# CANTRICK_MCU.net
KiCad netlist of a schematic drawn in Altium Designer
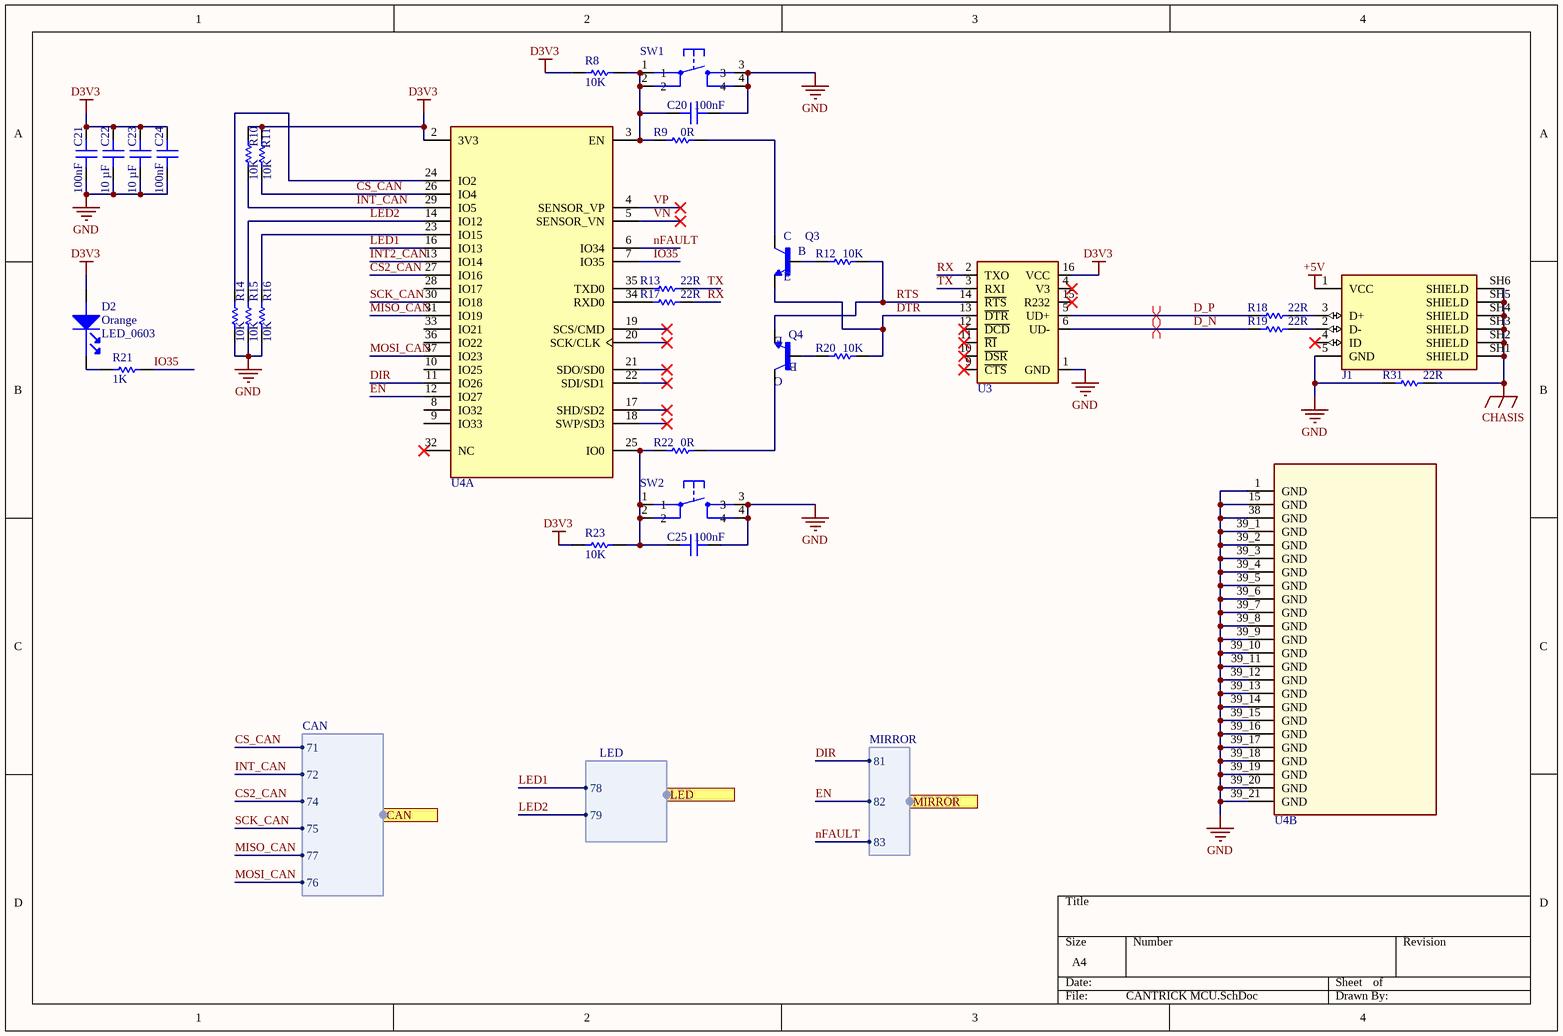
[diagram p0: CANTRICK MCU.SchDoc]

(export (version "E")
  (design (tool "Eeschema 10.0.6"))
  (components
    (comp (ref "C20")
      (value "100nF")
      (footprint "CAP 0603")
      (description "CAP0603 X7R 10UF 10% 10V")
      (fields
        (field (name "PART NUMBER") "GMC10X7R106K10NT")
        (field (name "MANUFACTURER") "Cal-Chip Electronics, Inc.")
      )
      (libsource (lib "Celestial Altium Library - altium_library") (part "Capacitor"))
    )
    (comp (ref "C21")
      (value "100nF")
      (footprint "CAP 0603")
      (description "CAP0603 X7R 10UF 10% 10V")
      (fields
        (field (name "PART NUMBER") "GMC10X7R106K10NT")
        (field (name "MANUFACTURER") "Cal-Chip Electronics, Inc.")
      )
      (libsource (lib "Celestial Altium Library - altium_library") (part "Capacitor"))
    )
    (comp (ref "C22")
      (value "10 µF")
      (footprint "CAP 0603")
      (description "CAP0603 X7R 10UF 10% 10V")
      (fields
        (field (name "PART NUMBER") "GMC10X7R106K10NT")
        (field (name "MANUFACTURER") "Cal-Chip Electronics, Inc.")
      )
      (libsource (lib "Celestial Altium Library - altium_library") (part "Capacitor"))
    )
    (comp (ref "C23")
      (value "10 µF")
      (footprint "CAP 0603")
      (description "CAP0603 X7R 10UF 10% 10V")
      (fields
        (field (name "PART NUMBER") "GMC10X7R106K10NT")
        (field (name "MANUFACTURER") "Cal-Chip Electronics, Inc.")
      )
      (libsource (lib "Celestial Altium Library - altium_library") (part "Capacitor"))
    )
    (comp (ref "C24")
      (value "100nF")
      (footprint "CAP 0603")
      (description "CAP0603 X7R 10UF 10% 10V")
      (fields
        (field (name "PART NUMBER") "GMC10X7R106K10NT")
        (field (name "MANUFACTURER") "Cal-Chip Electronics, Inc.")
      )
      (libsource (lib "Celestial Altium Library - altium_library") (part "Capacitor"))
    )
    (comp (ref "C25")
      (value "100nF")
      (footprint "CAP 0603")
      (description "CAP0603 X7R 10UF 10% 10V")
      (fields
        (field (name "PART NUMBER") "GMC10X7R106K10NT")
        (field (name "MANUFACTURER") "Cal-Chip Electronics, Inc.")
      )
      (libsource (lib "Celestial Altium Library - altium_library") (part "Capacitor"))
    )
    (comp (ref "D2")
      (value "Orange")
      (footprint "LED")
      (description "LED SMARTLED ORANGE 606NM 0603")
      (fields
        (field (name "MANUFACTURER") "OSRAM Opto Semiconductors Inc")
        (field (name "MANUFACTURER PART NUMBER") "LO L29K-H2K1-24-Z")
        (field (name "PACKAGE / CASE") "LED_0603")
        (field (name "BY") "Hieu.Nguyen_20191030")
      )
      (libsource (lib "Stm32_Flyback_Driver_250814_1") (part "LED ORANGE 606NM 0603"))
    )
    (comp (ref "J1")
      (value "MICRO B")
      (footprint "MICRO USB B")
      (libsource (lib "ESP32-S") (part "MICRO USB B"))
    )
    (comp (ref "Q3")
      (value "NMOS")
      (footprint "SOT23-3")
      (description "MMBT3904 Series 40 V CE Breakdown 0.2 A NPN General Purpose Amplifier - SOT-23")
      (fields (field (name "MANUFACTURER") "onsemi") (field (name "MANUFACTURER PART NUMBER") "MMBT3904"))
      (libsource (lib "") (part "MMBT3904_1"))
    )
    (comp (ref "Q4")
      (value "NMOS")
      (footprint "SOT23-3")
      (description "MMBT3904 Series 40 V CE Breakdown 0.2 A NPN General Purpose Amplifier - SOT-23")
      (fields (field (name "MANUFACTURER") "onsemi") (field (name "MANUFACTURER PART NUMBER") "MMBT3904"))
      (libsource (lib "Stm32_Flyback_Driver_250814_1") (part "MMBT3904"))
    )
    (comp (ref "R8")
      (value "10K")
      (footprint "Res 0603")
      (description "Res Thick Film 0603 2.2K Ohm 5% 1/10W ±200ppm/°C Molded SMD SMD Paper T/R")
      (fields
        (field (name "MANUFACTURER") "Vishay")
        (field (name "MANUFACTURER PART NUMBER") "CRCW06032K20JNEA")
      )
      (libsource (lib "Stm32_Flyback_Driver_250814_1") (part "Resistor 2.2K"))
    )
    (comp (ref "R9")
      (value "0R")
      (footprint "Res 0603")
      (description "Res Thick Film 0603 2.2K Ohm 5% 1/10W ±200ppm/°C Molded SMD SMD Paper T/R")
      (fields
        (field (name "MANUFACTURER") "Vishay")
        (field (name "MANUFACTURER PART NUMBER") "CRCW06032K20JNEA")
      )
      (libsource (lib "Stm32_Flyback_Driver_250814_1") (part "Resistor 2.2K"))
    )
    (comp (ref "R10")
      (value "10K")
      (footprint "Res 0603")
      (description "Res Thick Film 0603 2.2K Ohm 5% 1/10W ±200ppm/°C Molded SMD SMD Paper T/R")
      (fields
        (field (name "MANUFACTURER") "Vishay")
        (field (name "MANUFACTURER PART NUMBER") "CRCW06032K20JNEA")
      )
      (libsource (lib "Stm32_Flyback_Driver_250814_1") (part "Resistor 2.2K"))
    )
    (comp (ref "R11")
      (value "10K")
      (footprint "Res 0603")
      (description "Res Thick Film 0603 2.2K Ohm 5% 1/10W ±200ppm/°C Molded SMD SMD Paper T/R")
      (fields
        (field (name "MANUFACTURER") "Vishay")
        (field (name "MANUFACTURER PART NUMBER") "CRCW06032K20JNEA")
      )
      (libsource (lib "Stm32_Flyback_Driver_250814_1") (part "Resistor 2.2K"))
    )
    (comp (ref "R12")
      (value "10K")
      (footprint "Res 0603")
      (description "Res Thick Film 0603 2.2K Ohm 5% 1/10W ±200ppm/°C Molded SMD SMD Paper T/R")
      (fields
        (field (name "MANUFACTURER") "Vishay")
        (field (name "MANUFACTURER PART NUMBER") "CRCW06032K20JNEA")
      )
      (libsource (lib "Stm32_Flyback_Driver_250814_1") (part "Resistor 2.2K"))
    )
    (comp (ref "R13")
      (value "22R")
      (footprint "Res 0603")
      (description "Res Thick Film 0603 2.2K Ohm 5% 1/10W ±200ppm/°C Molded SMD SMD Paper T/R")
      (fields
        (field (name "MANUFACTURER") "Vishay")
        (field (name "MANUFACTURER PART NUMBER") "CRCW06032K20JNEA")
      )
      (libsource (lib "Stm32_Flyback_Driver_250814_1") (part "Resistor 2.2K"))
    )
    (comp (ref "R14")
      (value "10K")
      (footprint "Res 0603")
      (description "Res Thick Film 0603 2.2K Ohm 5% 1/10W ±200ppm/°C Molded SMD SMD Paper T/R")
      (fields
        (field (name "MANUFACTURER") "Vishay")
        (field (name "MANUFACTURER PART NUMBER") "CRCW06032K20JNEA")
      )
      (libsource (lib "Stm32_Flyback_Driver_250814_1") (part "Resistor 2.2K"))
    )
    (comp (ref "R15")
      (value "10K")
      (footprint "Res 0603")
      (description "Res Thick Film 0603 2.2K Ohm 5% 1/10W ±200ppm/°C Molded SMD SMD Paper T/R")
      (fields
        (field (name "MANUFACTURER") "Vishay")
        (field (name "MANUFACTURER PART NUMBER") "CRCW06032K20JNEA")
      )
      (libsource (lib "Stm32_Flyback_Driver_250814_1") (part "Resistor 2.2K"))
    )
    (comp (ref "R16")
      (value "10K")
      (footprint "Res 0603")
      (description "Res Thick Film 0603 2.2K Ohm 5% 1/10W ±200ppm/°C Molded SMD SMD Paper T/R")
      (fields
        (field (name "MANUFACTURER") "Vishay")
        (field (name "MANUFACTURER PART NUMBER") "CRCW06032K20JNEA")
      )
      (libsource (lib "Stm32_Flyback_Driver_250814_1") (part "Resistor 2.2K"))
    )
    (comp (ref "R17")
      (value "22R")
      (footprint "Res 0603")
      (description "Res Thick Film 0603 2.2K Ohm 5% 1/10W ±200ppm/°C Molded SMD SMD Paper T/R")
      (fields
        (field (name "MANUFACTURER") "Vishay")
        (field (name "MANUFACTURER PART NUMBER") "CRCW06032K20JNEA")
      )
      (libsource (lib "Stm32_Flyback_Driver_250814_1") (part "Resistor 2.2K"))
    )
    (comp (ref "R18")
      (value "22R")
      (footprint "Res 0603")
      (description "Res Thick Film 0603 2.2K Ohm 5% 1/10W ±200ppm/°C Molded SMD SMD Paper T/R")
      (fields
        (field (name "MANUFACTURER") "Vishay")
        (field (name "MANUFACTURER PART NUMBER") "CRCW06032K20JNEA")
      )
      (libsource (lib "Stm32_Flyback_Driver_250814_1") (part "Resistor 2.2K"))
    )
    (comp (ref "R19")
      (value "22R")
      (footprint "Res 0603")
      (description "Res Thick Film 0603 2.2K Ohm 5% 1/10W ±200ppm/°C Molded SMD SMD Paper T/R")
      (fields
        (field (name "MANUFACTURER") "Vishay")
        (field (name "MANUFACTURER PART NUMBER") "CRCW06032K20JNEA")
      )
      (libsource (lib "Stm32_Flyback_Driver_250814_1") (part "Resistor 2.2K"))
    )
    (comp (ref "R20")
      (value "10K")
      (footprint "Res 0603")
      (description "Res Thick Film 0603 2.2K Ohm 5% 1/10W ±200ppm/°C Molded SMD SMD Paper T/R")
      (fields
        (field (name "MANUFACTURER") "Vishay")
        (field (name "MANUFACTURER PART NUMBER") "CRCW06032K20JNEA")
      )
      (libsource (lib "Stm32_Flyback_Driver_250814_1") (part "Resistor 2.2K"))
    )
    (comp (ref "R21")
      (value "1K")
      (footprint "Res 0603")
      (description "Res Thick Film 0603 2.2K Ohm 5% 1/10W ±200ppm/°C Molded SMD SMD Paper T/R")
      (fields
        (field (name "MANUFACTURER") "Vishay")
        (field (name "MANUFACTURER PART NUMBER") "CRCW06032K20JNEA")
      )
      (libsource (lib "Stm32_Flyback_Driver_250814_1") (part "Resistor 2.2K"))
    )
    (comp (ref "R22")
      (value "0R")
      (footprint "Res 0603")
      (description "Res Thick Film 0603 2.2K Ohm 5% 1/10W ±200ppm/°C Molded SMD SMD Paper T/R")
      (fields
        (field (name "MANUFACTURER") "Vishay")
        (field (name "MANUFACTURER PART NUMBER") "CRCW06032K20JNEA")
      )
      (libsource (lib "Stm32_Flyback_Driver_250814_1") (part "Resistor 2.2K"))
    )
    (comp (ref "R23")
      (value "10K")
      (footprint "Res 0603")
      (description "Res Thick Film 0603 2.2K Ohm 5% 1/10W ±200ppm/°C Molded SMD SMD Paper T/R")
      (fields
        (field (name "MANUFACTURER") "Vishay")
        (field (name "MANUFACTURER PART NUMBER") "CRCW06032K20JNEA")
      )
      (libsource (lib "Stm32_Flyback_Driver_250814_1") (part "Resistor 2.2K"))
    )
    (comp (ref "R31")
      (value "22R")
      (footprint "Res 0603")
      (description "Res Thick Film 0603 2.2K Ohm 5% 1/10W ±200ppm/°C Molded SMD SMD Paper T/R")
      (fields
        (field (name "MANUFACTURER") "Vishay")
        (field (name "MANUFACTURER PART NUMBER") "CRCW06032K20JNEA")
      )
      (libsource (lib "Stm32_Flyback_Driver_250814_1") (part "Resistor 2.2K"))
    )
    (comp (ref "SW1")
      (value "SW2")
      (footprint "SWITCH")
      (description "Switch button 4 pin")
      (libsource (lib "Stm32_Flyback_Driver_250814_1") (part "SW2"))
    )
    (comp (ref "SW2")
      (value "SW2")
      (footprint "SWITCH")
      (description "Switch button 4 pin")
      (libsource (lib "Stm32_Flyback_Driver_250814_1") (part "SW2"))
    )
    (comp (ref "U3") (value "CH340C") (footprint "CH340C") (libsource (lib "ESP32-S") (part "CH340C")))
    (comp (ref "U4")
      (value "ESP32-WROOM-32UE-N8")
      (footprint "ESP32S")
      (description "Multiprotocol Modules SMD module ESP32-WROOM-32UE, ESP32-D0WD-V3, ESP32 ECO V3,")
      (fields (field (name "MANUFACTURER") "Espressif Systems"))
      (libsource (lib "ESP32-S") (part "ESP32-WROOM-32UE-N8"))
    )
  )
  (nets
    (net (code "4") (name "+5V") (class "Default")
      (node (ref "J1") (pin "1") (pinfunction "VCC_1") (pintype "power_in"))
    )
    (net (code "5") (name "/CS2_CAN") (class "Default")
      (node (ref "U4") (pin "27") (pinfunction "IO16_27") (pintype "passive"))
    )
    (net (code "6") (name "/CS_CAN") (class "Default")
      (node (ref "R11") (pin "1") (pinfunction "1_1") (pintype "passive"))
      (node (ref "U4") (pin "26") (pinfunction "IO4_26") (pintype "passive"))
    )
    (net (code "7") (name "/DIR") (class "Default")
      (node (ref "U4") (pin "11") (pinfunction "IO26_11") (pintype "passive"))
    )
    (net (code "8") (name "/DTR") (class "Default")
      (node (ref "Q3") (pin "2") (pinfunction "E_2") (pintype "passive"))
      (node (ref "R20") (pin "2") (pinfunction "2_2") (pintype "passive"))
      (node (ref "U3") (pin "13") (pinfunction "~{DTR}_13") (pintype "passive"))
    )
    (net (code "9") (name "/D_N") (class "Default")
      (node (ref "R19") (pin "1") (pinfunction "1_1") (pintype "passive"))
      (node (ref "U3") (pin "6") (pinfunction "UD-_6") (pintype "passive"))
    )
    (net (code "10") (name "/D_P") (class "Default")
      (node (ref "R18") (pin "1") (pinfunction "1_1") (pintype "passive"))
      (node (ref "U3") (pin "5") (pinfunction "UD+_5") (pintype "passive"))
    )
    (net (code "11") (name "/EN") (class "Default")
      (node (ref "U4") (pin "12") (pinfunction "IO27_12") (pintype "passive"))
    )
    (net (code "12") (name "/INT2_CAN") (class "Default")
      (node (ref "U4") (pin "13") (pinfunction "IO14_13") (pintype "passive"))
    )
    (net (code "13") (name "/INT_CAN") (class "Default")
      (node (ref "R10") (pin "1") (pinfunction "1_1") (pintype "passive"))
      (node (ref "U4") (pin "29") (pinfunction "IO5_29") (pintype "passive"))
    )
    (net (code "14") (name "/IO35") (class "Default")
      (node (ref "R21") (pin "2") (pinfunction "2_2") (pintype "passive"))
      (node (ref "U4") (pin "7") (pinfunction "IO35_7") (pintype "passive"))
    )
    (net (code "15") (name "/LED1") (class "Default")
      (node (ref "U4") (pin "16") (pinfunction "IO13_16") (pintype "passive"))
    )
    (net (code "16") (name "/LED2") (class "Default")
      (node (ref "R15") (pin "2") (pinfunction "2_2") (pintype "passive"))
      (node (ref "U4") (pin "14") (pinfunction "IO12_14") (pintype "passive"))
    )
    (net (code "17") (name "/MISO_CAN") (class "Default")
      (node (ref "U4") (pin "31") (pinfunction "IO19_31") (pintype "passive"))
    )
    (net (code "18") (name "/MOSI_CAN") (class "Default")
      (node (ref "U4") (pin "37") (pinfunction "IO23_37") (pintype "passive"))
    )
    (net (code "19") (name "/RTS") (class "Default")
      (node (ref "Q4") (pin "2") (pinfunction "E_2") (pintype "passive"))
      (node (ref "R12") (pin "2") (pinfunction "2_2") (pintype "passive"))
      (node (ref "U3") (pin "14") (pinfunction "~{RTS}_14") (pintype "passive"))
    )
    (net (code "20") (name "/RX") (class "Default")
      (node (ref "R17") (pin "2") (pinfunction "2_2") (pintype "passive"))
      (node (ref "U3") (pin "2") (pinfunction "TXO_2") (pintype "passive"))
    )
    (net (code "21") (name "/SCK_CAN") (class "Default")
      (node (ref "U4") (pin "30") (pinfunction "IO18_30") (pintype "passive"))
    )
    (net (code "22") (name "/TX") (class "Default")
      (node (ref "R13") (pin "2") (pinfunction "2_2") (pintype "passive"))
      (node (ref "U3") (pin "3") (pinfunction "RXI_3") (pintype "passive"))
    )
    (net (code "23") (name "/VN") (class "Default")
      (node (ref "U4") (pin "5") (pinfunction "SENSOR_VN_5") (pintype "passive+no_connect"))
    )
    (net (code "24") (name "/VP") (class "Default")
      (node (ref "U4") (pin "4") (pinfunction "SENSOR_VP_4") (pintype "passive+no_connect"))
    )
    (net (code "25") (name "/nFAULT") (class "Default")
      (node (ref "U4") (pin "6") (pinfunction "IO34_6") (pintype "passive"))
    )
    (net (code "29") (name "CHASIS") (class "Default")
      (node (ref "J1") (pin "SH1") (pinfunction "SHIELD_SH1") (pintype "passive"))
      (node (ref "J1") (pin "SH2") (pinfunction "SHIELD_SH2") (pintype "passive"))
      (node (ref "J1") (pin "SH3") (pinfunction "SHIELD_SH3") (pintype "passive"))
      (node (ref "J1") (pin "SH4") (pinfunction "SHIELD_SH4") (pintype "passive"))
      (node (ref "J1") (pin "SH5") (pinfunction "SHIELD_SH5") (pintype "passive"))
      (node (ref "J1") (pin "SH6") (pinfunction "SHIELD_SH6") (pintype "passive"))
      (node (ref "R31") (pin "2") (pinfunction "2_2") (pintype "passive"))
    )
    (net (code "30") (name "D3V3") (class "Default")
      (node (ref "C21") (pin "2") (pinfunction "2_2") (pintype "passive"))
      (node (ref "C22") (pin "2") (pinfunction "2_2") (pintype "passive"))
      (node (ref "C23") (pin "2") (pinfunction "2_2") (pintype "passive"))
      (node (ref "C24") (pin "2") (pinfunction "2_2") (pintype "passive"))
      (node (ref "D2") (pin "1") (pinfunction "ANODE_1") (pintype "passive"))
      (node (ref "R10") (pin "2") (pinfunction "2_2") (pintype "passive"))
      (node (ref "R11") (pin "2") (pinfunction "2_2") (pintype "passive"))
      (node (ref "R23") (pin "1") (pinfunction "1_1") (pintype "passive"))
      (node (ref "R8") (pin "1") (pinfunction "1_1") (pintype "passive"))
      (node (ref "U3") (pin "16") (pinfunction "VCC_16") (pintype "passive"))
      (node (ref "U4") (pin "2") (pinfunction "3V3_2") (pintype "passive"))
    )
    (net (code "31") (name "GND") (class "Default")
      (node (ref "C20") (pin "1") (pinfunction "1_1") (pintype "passive"))
      (node (ref "C21") (pin "1") (pinfunction "1_1") (pintype "passive"))
      (node (ref "C22") (pin "1") (pinfunction "1_1") (pintype "passive"))
      (node (ref "C23") (pin "1") (pinfunction "1_1") (pintype "passive"))
      (node (ref "C24") (pin "1") (pinfunction "1_1") (pintype "passive"))
      (node (ref "C25") (pin "1") (pinfunction "1_1") (pintype "passive"))
      (node (ref "J1") (pin "5") (pinfunction "GND_5") (pintype "power_in"))
      (node (ref "R14") (pin "1") (pinfunction "1_1") (pintype "passive"))
      (node (ref "R15") (pin "1") (pinfunction "1_1") (pintype "passive"))
      (node (ref "R16") (pin "1") (pinfunction "1_1") (pintype "passive"))
      (node (ref "R31") (pin "1") (pinfunction "1_1") (pintype "passive"))
      (node (ref "SW1") (pin "3") (pinfunction "3_3") (pintype "passive"))
      (node (ref "SW1") (pin "4") (pinfunction "4_4") (pintype "passive"))
      (node (ref "SW2") (pin "3") (pinfunction "3_3") (pintype "passive"))
      (node (ref "SW2") (pin "4") (pinfunction "4_4") (pintype "passive"))
      (node (ref "U3") (pin "1") (pinfunction "GND_1") (pintype "passive"))
      (node (ref "U4") (pin "1") (pinfunction "GND_1") (pintype "passive"))
      (node (ref "U4") (pin "15") (pinfunction "GND_15") (pintype "passive"))
      (node (ref "U4") (pin "38") (pinfunction "GND_38") (pintype "passive"))
      (node (ref "U4") (pin "39_1") (pinfunction "GND_39_1") (pintype "passive"))
      (node (ref "U4") (pin "39_10") (pinfunction "GND_39_10") (pintype "passive"))
      (node (ref "U4") (pin "39_11") (pinfunction "GND_39_11") (pintype "passive"))
      (node (ref "U4") (pin "39_12") (pinfunction "GND_39_12") (pintype "passive"))
      (node (ref "U4") (pin "39_13") (pinfunction "GND_39_13") (pintype "passive"))
      (node (ref "U4") (pin "39_14") (pinfunction "GND_39_14") (pintype "passive"))
      (node (ref "U4") (pin "39_15") (pinfunction "GND_39_15") (pintype "passive"))
      (node (ref "U4") (pin "39_16") (pinfunction "GND_39_16") (pintype "passive"))
      (node (ref "U4") (pin "39_17") (pinfunction "GND_39_17") (pintype "passive"))
      (node (ref "U4") (pin "39_18") (pinfunction "GND_39_18") (pintype "passive"))
      (node (ref "U4") (pin "39_19") (pinfunction "GND_39_19") (pintype "passive"))
      (node (ref "U4") (pin "39_2") (pinfunction "GND_39_2") (pintype "passive"))
      (node (ref "U4") (pin "39_20") (pinfunction "GND_39_20") (pintype "passive"))
      (node (ref "U4") (pin "39_21") (pinfunction "GND_39_21") (pintype "passive"))
      (node (ref "U4") (pin "39_3") (pinfunction "GND_39_3") (pintype "passive"))
      (node (ref "U4") (pin "39_4") (pinfunction "GND_39_4") (pintype "passive"))
      (node (ref "U4") (pin "39_5") (pinfunction "GND_39_5") (pintype "passive"))
      (node (ref "U4") (pin "39_6") (pinfunction "GND_39_6") (pintype "passive"))
      (node (ref "U4") (pin "39_7") (pinfunction "GND_39_7") (pintype "passive"))
      (node (ref "U4") (pin "39_8") (pinfunction "GND_39_8") (pintype "passive"))
      (node (ref "U4") (pin "39_9") (pinfunction "GND_39_9") (pintype "passive"))
    )
    (net (code "32") (name "Net-(D2-cathode)") (class "Default")
      (node (ref "D2") (pin "2") (pinfunction "cathode_2") (pintype "passive"))
      (node (ref "R21") (pin "1") (pinfunction "1_1") (pintype "passive"))
    )
    (net (code "33") (name "Net-(J1-D+)") (class "Default")
      (node (ref "J1") (pin "3") (pinfunction "D+_3") (pintype "bidirectional"))
      (node (ref "R18") (pin "2") (pinfunction "2_2") (pintype "passive"))
    )
    (net (code "34") (name "Net-(J1-D-)") (class "Default")
      (node (ref "J1") (pin "2") (pinfunction "D-_2") (pintype "bidirectional"))
      (node (ref "R19") (pin "2") (pinfunction "2_2") (pintype "passive"))
    )
    (net (code "35") (name "Net-(Q3-B)") (class "Default")
      (node (ref "Q3") (pin "1") (pinfunction "B_1") (pintype "passive"))
      (node (ref "R12") (pin "1") (pinfunction "1_1") (pintype "passive"))
    )
    (net (code "36") (name "Net-(Q3-C)") (class "Default")
      (node (ref "Q3") (pin "3") (pinfunction "C_3") (pintype "passive"))
      (node (ref "R9") (pin "2") (pinfunction "2_2") (pintype "passive"))
    )
    (net (code "37") (name "Net-(Q4-B)") (class "Default")
      (node (ref "Q4") (pin "1") (pinfunction "B_1") (pintype "passive"))
      (node (ref "R20") (pin "1") (pinfunction "1_1") (pintype "passive"))
    )
    (net (code "38") (name "Net-(Q4-C)") (class "Default")
      (node (ref "Q4") (pin "3") (pinfunction "C_3") (pintype "passive"))
      (node (ref "R22") (pin "2") (pinfunction "2_2") (pintype "passive"))
    )
    (net (code "39") (name "Net-(U4A-EN)") (class "Default")
      (node (ref "C20") (pin "2") (pinfunction "2_2") (pintype "passive"))
      (node (ref "R8") (pin "2") (pinfunction "2_2") (pintype "passive"))
      (node (ref "R9") (pin "1") (pinfunction "1_1") (pintype "passive"))
      (node (ref "SW1") (pin "1") (pinfunction "1_1") (pintype "passive"))
      (node (ref "SW1") (pin "2") (pinfunction "2_2") (pintype "passive"))
      (node (ref "U4") (pin "3") (pinfunction "EN_3") (pintype "passive"))
    )
    (net (code "40") (name "Net-(U4A-IO0)") (class "Default")
      (node (ref "C25") (pin "2") (pinfunction "2_2") (pintype "passive"))
      (node (ref "R22") (pin "1") (pinfunction "1_1") (pintype "passive"))
      (node (ref "R23") (pin "2") (pinfunction "2_2") (pintype "passive"))
      (node (ref "SW2") (pin "1") (pinfunction "1_1") (pintype "passive"))
      (node (ref "SW2") (pin "2") (pinfunction "2_2") (pintype "passive"))
      (node (ref "U4") (pin "25") (pinfunction "IO0_25") (pintype "passive"))
    )
    (net (code "41") (name "Net-(U4A-IO2)") (class "Default")
      (node (ref "R14") (pin "2") (pinfunction "2_2") (pintype "passive"))
      (node (ref "U4") (pin "24") (pinfunction "IO2_24") (pintype "passive"))
    )
    (net (code "42") (name "Net-(U4A-IO15)") (class "Default")
      (node (ref "R16") (pin "2") (pinfunction "2_2") (pintype "passive"))
      (node (ref "U4") (pin "23") (pinfunction "IO15_23") (pintype "passive"))
    )
    (net (code "43") (name "Net-(U4A-RXD0)") (class "Default")
      (node (ref "R17") (pin "1") (pinfunction "1_1") (pintype "passive"))
      (node (ref "U4") (pin "34") (pinfunction "RXD0_34") (pintype "passive"))
    )
    (net (code "44") (name "Net-(U4A-TXD0)") (class "Default")
      (node (ref "R13") (pin "1") (pinfunction "1_1") (pintype "passive"))
      (node (ref "U4") (pin "35") (pinfunction "TXD0_35") (pintype "passive"))
    )
    (net (code "45") (name "unconnected-(J1-ID-Pad4)") (class "Default")
      (node (ref "J1") (pin "4") (pinfunction "ID_4") (pintype "bidirectional+no_connect"))
    )
    (net (code "46") (name "unconnected-(U3-R232-Pad15)") (class "Default")
      (node (ref "U3") (pin "15") (pinfunction "R232_15") (pintype "passive+no_connect"))
    )
    (net (code "47") (name "unconnected-(U3-V3-Pad4)") (class "Default")
      (node (ref "U3") (pin "4") (pinfunction "V3_4") (pintype "passive+no_connect"))
    )
    (net (code "48") (name "unconnected-(U3-~{CTS}-Pad9)") (class "Default")
      (node (ref "U3") (pin "9") (pinfunction "~{CTS}_9") (pintype "passive+no_connect"))
    )
    (net (code "49") (name "unconnected-(U3-~{DCD}-Pad12)") (class "Default")
      (node (ref "U3") (pin "12") (pinfunction "~{DCD}_12") (pintype "passive+no_connect"))
    )
    (net (code "50") (name "unconnected-(U3-~{DSR}-Pad10)") (class "Default")
      (node (ref "U3") (pin "10") (pinfunction "~{DSR}_10") (pintype "passive+no_connect"))
    )
    (net (code "51") (name "unconnected-(U3-~{RI}-Pad11)") (class "Default")
      (node (ref "U3") (pin "11") (pinfunction "~{RI}_11") (pintype "passive+no_connect"))
    )
    (net (code "52") (name "unconnected-(U4A-IO17-Pad28)") (class "Default")
      (node (ref "U4") (pin "28") (pinfunction "IO17_28") (pintype "passive"))
    )
    (net (code "53") (name "unconnected-(U4A-IO21-Pad33)") (class "Default")
      (node (ref "U4") (pin "33") (pinfunction "IO21_33") (pintype "passive"))
    )
    (net (code "54") (name "unconnected-(U4A-IO22-Pad36)") (class "Default")
      (node (ref "U4") (pin "36") (pinfunction "IO22_36") (pintype "passive"))
    )
    (net (code "55") (name "unconnected-(U4A-IO25-Pad10)") (class "Default")
      (node (ref "U4") (pin "10") (pinfunction "IO25_10") (pintype "passive"))
    )
    (net (code "56") (name "unconnected-(U4A-IO32-Pad8)") (class "Default")
      (node (ref "U4") (pin "8") (pinfunction "IO32_8") (pintype "passive"))
    )
    (net (code "57") (name "unconnected-(U4A-IO33-Pad9)") (class "Default")
      (node (ref "U4") (pin "9") (pinfunction "IO33_9") (pintype "passive"))
    )
    (net (code "58") (name "unconnected-(U4A-NC-Pad32)") (class "Default")
      (node (ref "U4") (pin "32") (pinfunction "NC_32") (pintype "passive+no_connect"))
    )
    (net (code "59") (name "unconnected-(U4A-SCK{slash}CLK-Pad20)") (class "Default")
      (node (ref "U4") (pin "20") (pinfunction "SCK/CLK_20") (pintype "passive+no_connect"))
    )
    (net (code "60") (name "unconnected-(U4A-SCS{slash}CMD-Pad19)") (class "Default")
      (node (ref "U4") (pin "19") (pinfunction "SCS/CMD_19") (pintype "passive+no_connect"))
    )
    (net (code "61") (name "unconnected-(U4A-SDI{slash}SD1-Pad22)") (class "Default")
      (node (ref "U4") (pin "22") (pinfunction "SDI/SD1_22") (pintype "passive+no_connect"))
    )
    (net (code "62") (name "unconnected-(U4A-SDO{slash}SD0-Pad21)") (class "Default")
      (node (ref "U4") (pin "21") (pinfunction "SDO/SD0_21") (pintype "passive+no_connect"))
    )
    (net (code "63") (name "unconnected-(U4A-SHD{slash}SD2-Pad17)") (class "Default")
      (node (ref "U4") (pin "17") (pinfunction "SHD/SD2_17") (pintype "passive+no_connect"))
    )
    (net (code "64") (name "unconnected-(U4A-SWP{slash}SD3-Pad18)") (class "Default")
      (node (ref "U4") (pin "18") (pinfunction "SWP/SD3_18") (pintype "passive+no_connect"))
    )
  )
)
